# top.net
KiCad netlist of a schematic drawn in Altium Designer
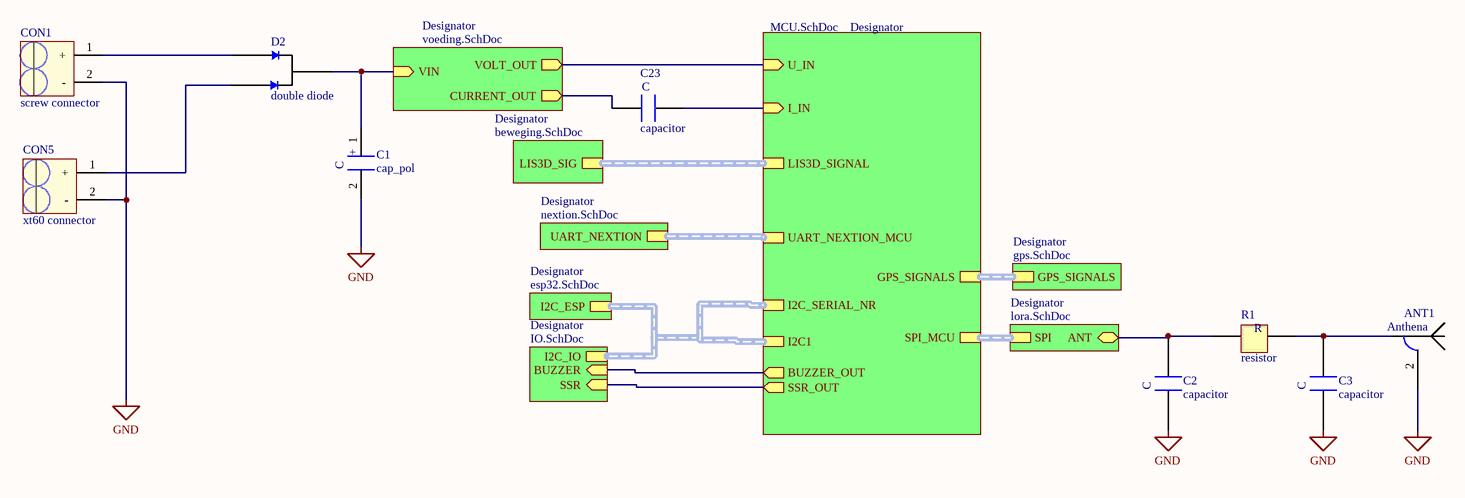
[diagram p0: top.SchDoc]

(export (version "E")
  (design (tool "Eeschema 10.0.6"))
  (components
    (comp (ref "ANT1")
      (value "Anthena")
      (footprint "sma connector")
      (libsource (lib "pasives") (part "Anthena"))
    )
    (comp (ref "C1") (value "cap_pol") (footprint "1206") (libsource (lib "pasives") (part "cap_pol")))
    (comp (ref "C2") (value "capacitor") (footprint "0603") (libsource (lib "pasives") (part "capacitor")))
    (comp (ref "C3") (value "capacitor") (footprint "0603") (libsource (lib "pasives") (part "capacitor")))
    (comp (ref "C23") (value "capacitor") (footprint "0603") (libsource (lib "") (part "capacitor_1")))
    (comp (ref "CON1")
      (value "screw connector")
      (footprint "SCREW connector 5mm pitch")
      (libsource (lib "conector's_and_TP") (part "screw connector"))
    )
    (comp (ref "CON5")
      (value "xt60 connector")
      (description "screw connector")
      (libsource (lib "conector's_and_TP") (part "screw connector"))
    )
    (comp (ref "D2")
      (value "double diode")
      (footprint "TO-263AB")
      (libsource (lib "halfgelijders") (part "double diode"))
    )
    (comp (ref "R1") (value "resistor") (footprint "0603") (libsource (lib "pasives") (part "resistor")))
  )
  (nets
    (net (code "1") (name "/ANT") (class "Default")
      (node (ref "C2") (pin "1") (pinfunction "1_1") (pintype "passive"))
      (node (ref "R1") (pin "2") (pinfunction "2_2") (pintype "passive"))
    )
    (net (code "3") (name "/CURRENT_OUT") (class "Default")
      (node (ref "C23") (pin "2") (pinfunction "2_2") (pintype "passive"))
    )
    (net (code "6") (name "/I_IN") (class "Default")
      (node (ref "C23") (pin "1") (pinfunction "1_1") (pintype "passive"))
    )
    (net (code "11") (name "/VIN") (class "Default")
      (node (ref "C1") (pin "1") (pinfunction "1_1") (pintype "passive"))
      (node (ref "D2") (pin "3") (pinfunction "3_3") (pintype "passive"))
    )
    (net (code "13") (name "GND") (class "Default")
      (node (ref "ANT1") (pin "2") (pinfunction "2_2") (pintype "passive"))
      (node (ref "C1") (pin "2") (pinfunction "2_2") (pintype "passive"))
      (node (ref "C2") (pin "2") (pinfunction "2_2") (pintype "passive"))
      (node (ref "C3") (pin "2") (pinfunction "2_2") (pintype "passive"))
      (node (ref "CON1") (pin "2") (pinfunction "-_2") (pintype "passive"))
      (node (ref "CON5") (pin "2") (pinfunction "-_2") (pintype "passive"))
    )
    (net (code "14") (name "Net-(ANT1-Pad1)") (class "Default")
      (node (ref "ANT1") (pin "1") (pinfunction "1_1") (pintype "passive"))
      (node (ref "C3") (pin "1") (pinfunction "1_1") (pintype "passive"))
      (node (ref "R1") (pin "1") (pinfunction "1_1") (pintype "passive"))
    )
    (net (code "15") (name "Net-(CON1-+)") (class "Default")
      (node (ref "CON1") (pin "1") (pinfunction "+_1") (pintype "passive"))
      (node (ref "D2") (pin "1") (pinfunction "1_1") (pintype "passive"))
    )
    (net (code "16") (name "Net-(CON5-+)") (class "Default")
      (node (ref "CON5") (pin "1") (pinfunction "+_1") (pintype "passive"))
      (node (ref "D2") (pin "2") (pinfunction "2_2") (pintype "passive"))
    )
  )
)
